# BMS_Adapter_Segment_millable.net
KiCad netlist of a schematic drawn in EAGLE
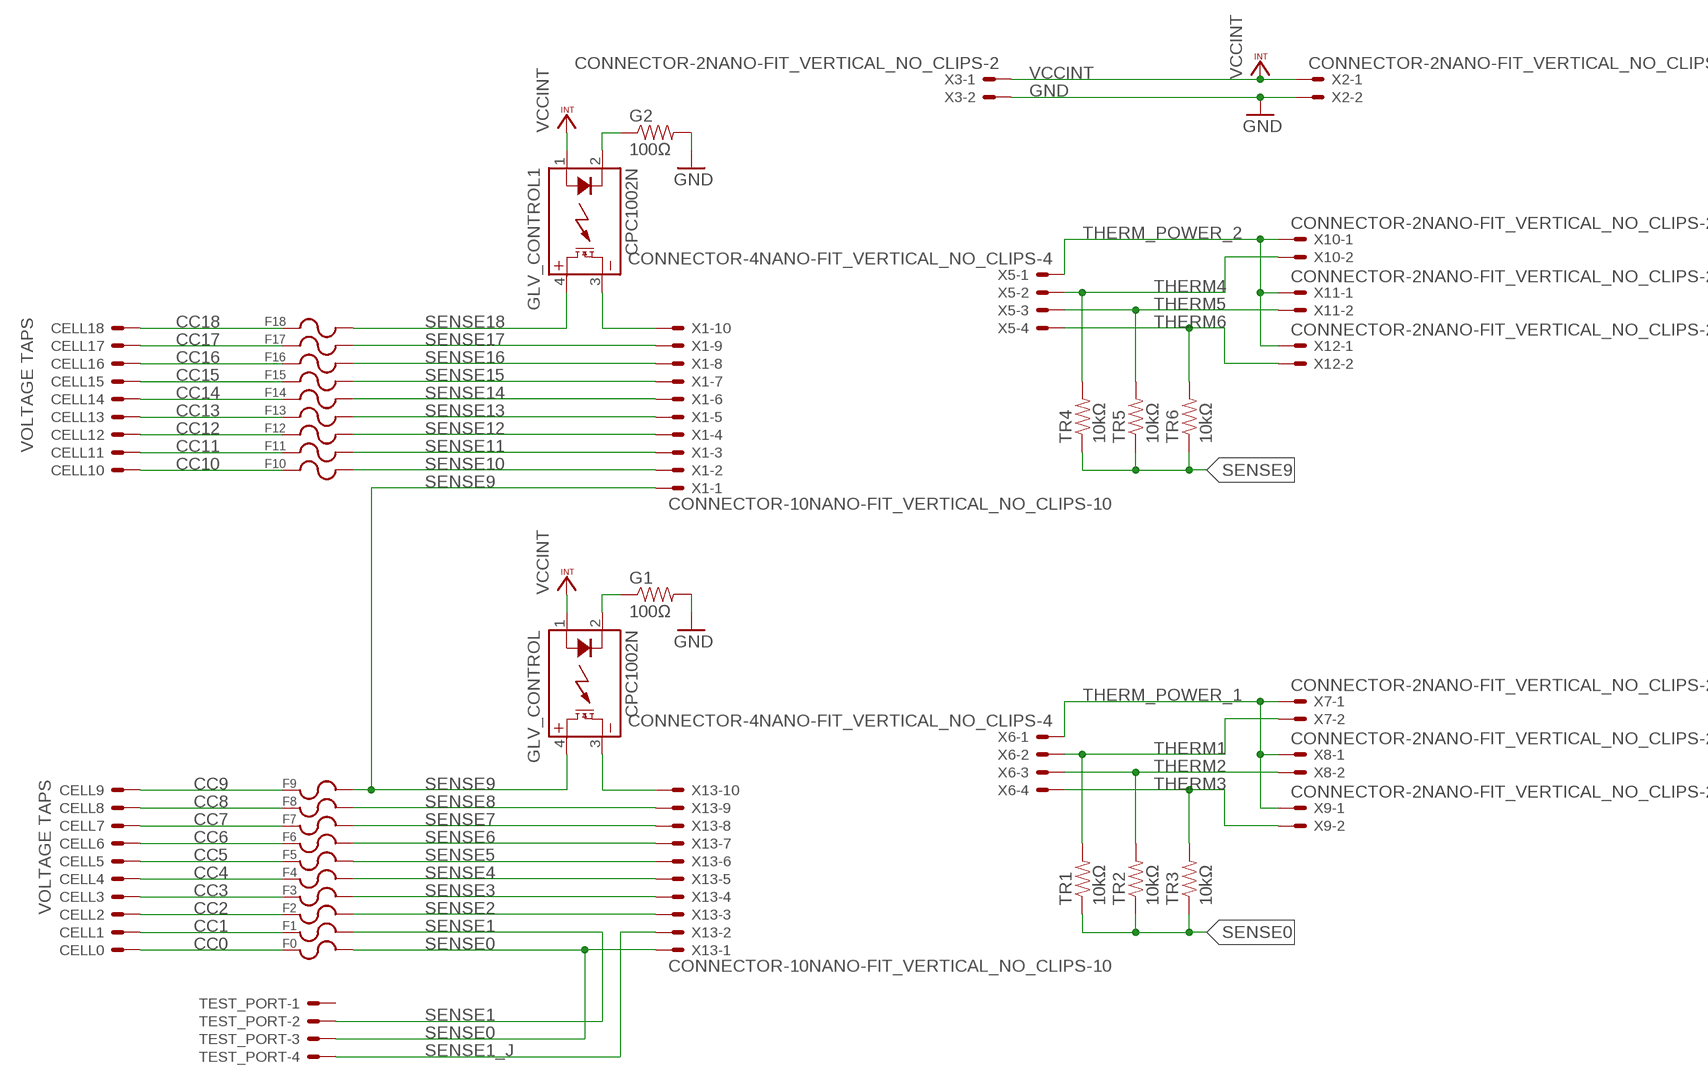
[diagram p0: schematic, sheet 1]

(export (version "E")
  (design (tool "Eeschema 10.0.6"))
  (components
    (comp (ref "CELL0")
      (value "BATTERY_SPRING_KEYSTONE5222")
      (footprint "eagle-import:KEYSTONE5222")
      (libsource (lib "eagle-import") (part "BATTERY_SPRING_KEYSTONE5222"))
    )
    (comp (ref "CELL1")
      (value "BATTERY_SPRING_KEYSTONE5222")
      (footprint "eagle-import:KEYSTONE5222")
      (libsource (lib "eagle-import") (part "BATTERY_SPRING_KEYSTONE5222"))
    )
    (comp (ref "CELL2")
      (value "BATTERY_SPRING_KEYSTONE5222")
      (footprint "eagle-import:KEYSTONE5222")
      (libsource (lib "eagle-import") (part "BATTERY_SPRING_KEYSTONE5222"))
    )
    (comp (ref "CELL3")
      (value "BATTERY_SPRING_KEYSTONE5222")
      (footprint "eagle-import:KEYSTONE5222")
      (libsource (lib "eagle-import") (part "BATTERY_SPRING_KEYSTONE5222"))
    )
    (comp (ref "CELL4")
      (value "BATTERY_SPRING_KEYSTONE5222")
      (footprint "eagle-import:KEYSTONE5222")
      (libsource (lib "eagle-import") (part "BATTERY_SPRING_KEYSTONE5222"))
    )
    (comp (ref "CELL5")
      (value "BATTERY_SPRING_KEYSTONE5222")
      (footprint "eagle-import:KEYSTONE5222")
      (libsource (lib "eagle-import") (part "BATTERY_SPRING_KEYSTONE5222"))
    )
    (comp (ref "CELL6")
      (value "BATTERY_SPRING_KEYSTONE5222")
      (footprint "eagle-import:KEYSTONE5222")
      (libsource (lib "eagle-import") (part "BATTERY_SPRING_KEYSTONE5222"))
    )
    (comp (ref "CELL7")
      (value "BATTERY_SPRING_KEYSTONE5222")
      (footprint "eagle-import:KEYSTONE5222")
      (libsource (lib "eagle-import") (part "BATTERY_SPRING_KEYSTONE5222"))
    )
    (comp (ref "CELL8")
      (value "BATTERY_SPRING_KEYSTONE5222")
      (footprint "eagle-import:KEYSTONE5222")
      (libsource (lib "eagle-import") (part "BATTERY_SPRING_KEYSTONE5222"))
    )
    (comp (ref "CELL9")
      (value "BATTERY_SPRING_KEYSTONE5222")
      (footprint "eagle-import:KEYSTONE5222")
      (libsource (lib "eagle-import") (part "BATTERY_SPRING_KEYSTONE5222"))
    )
    (comp (ref "CELL10")
      (value "BATTERY_SPRING_KEYSTONE5222")
      (footprint "eagle-import:KEYSTONE5222")
      (libsource (lib "eagle-import") (part "BATTERY_SPRING_KEYSTONE5222"))
    )
    (comp (ref "CELL11")
      (value "BATTERY_SPRING_KEYSTONE5222")
      (footprint "eagle-import:KEYSTONE5222")
      (libsource (lib "eagle-import") (part "BATTERY_SPRING_KEYSTONE5222"))
    )
    (comp (ref "CELL12")
      (value "BATTERY_SPRING_KEYSTONE5222")
      (footprint "eagle-import:KEYSTONE5222")
      (libsource (lib "eagle-import") (part "BATTERY_SPRING_KEYSTONE5222"))
    )
    (comp (ref "CELL13")
      (value "BATTERY_SPRING_KEYSTONE5222")
      (footprint "eagle-import:KEYSTONE5222")
      (libsource (lib "eagle-import") (part "BATTERY_SPRING_KEYSTONE5222"))
    )
    (comp (ref "CELL14")
      (value "BATTERY_SPRING_KEYSTONE5222")
      (footprint "eagle-import:KEYSTONE5222")
      (libsource (lib "eagle-import") (part "BATTERY_SPRING_KEYSTONE5222"))
    )
    (comp (ref "CELL15")
      (value "BATTERY_SPRING_KEYSTONE5222")
      (footprint "eagle-import:KEYSTONE5222")
      (libsource (lib "eagle-import") (part "BATTERY_SPRING_KEYSTONE5222"))
    )
    (comp (ref "CELL16")
      (value "BATTERY_SPRING_KEYSTONE5222")
      (footprint "eagle-import:KEYSTONE5222")
      (libsource (lib "eagle-import") (part "BATTERY_SPRING_KEYSTONE5222"))
    )
    (comp (ref "CELL17")
      (value "BATTERY_SPRING_KEYSTONE5222")
      (footprint "eagle-import:KEYSTONE5222")
      (libsource (lib "eagle-import") (part "BATTERY_SPRING_KEYSTONE5222"))
    )
    (comp (ref "CELL18")
      (value "BATTERY_SPRING_KEYSTONE5222")
      (footprint "eagle-import:KEYSTONE5222")
      (libsource (lib "eagle-import") (part "BATTERY_SPRING_KEYSTONE5222"))
    )
    (comp (ref "F0")
      (value "0751.0110_FUSE_CLIP")
      (footprint "eagle-import:0751.0110")
      (libsource (lib "eagle-import") (part "0751.0110_FUSE_CLIP"))
    )
    (comp (ref "F1")
      (value "0751.0110_FUSE_CLIP")
      (footprint "eagle-import:0751.0110")
      (libsource (lib "eagle-import") (part "0751.0110_FUSE_CLIP"))
    )
    (comp (ref "F2")
      (value "0751.0110_FUSE_CLIP")
      (footprint "eagle-import:0751.0110")
      (libsource (lib "eagle-import") (part "0751.0110_FUSE_CLIP"))
    )
    (comp (ref "F3")
      (value "0751.0110_FUSE_CLIP")
      (footprint "eagle-import:0751.0110")
      (libsource (lib "eagle-import") (part "0751.0110_FUSE_CLIP"))
    )
    (comp (ref "F4")
      (value "0751.0110_FUSE_CLIP")
      (footprint "eagle-import:0751.0110")
      (libsource (lib "eagle-import") (part "0751.0110_FUSE_CLIP"))
    )
    (comp (ref "F5")
      (value "0751.0110_FUSE_CLIP")
      (footprint "eagle-import:0751.0110")
      (libsource (lib "eagle-import") (part "0751.0110_FUSE_CLIP"))
    )
    (comp (ref "F6")
      (value "0751.0110_FUSE_CLIP")
      (footprint "eagle-import:0751.0110")
      (libsource (lib "eagle-import") (part "0751.0110_FUSE_CLIP"))
    )
    (comp (ref "F7")
      (value "0751.0110_FUSE_CLIP")
      (footprint "eagle-import:0751.0110")
      (libsource (lib "eagle-import") (part "0751.0110_FUSE_CLIP"))
    )
    (comp (ref "F8")
      (value "0751.0110_FUSE_CLIP")
      (footprint "eagle-import:0751.0110")
      (libsource (lib "eagle-import") (part "0751.0110_FUSE_CLIP"))
    )
    (comp (ref "F9")
      (value "0751.0110_FUSE_CLIP")
      (footprint "eagle-import:0751.0110")
      (libsource (lib "eagle-import") (part "0751.0110_FUSE_CLIP"))
    )
    (comp (ref "F10")
      (value "0751.0110_FUSE_CLIP")
      (footprint "eagle-import:0751.0110")
      (libsource (lib "eagle-import") (part "0751.0110_FUSE_CLIP"))
    )
    (comp (ref "F11")
      (value "0751.0110_FUSE_CLIP")
      (footprint "eagle-import:0751.0110")
      (libsource (lib "eagle-import") (part "0751.0110_FUSE_CLIP"))
    )
    (comp (ref "F12")
      (value "0751.0110_FUSE_CLIP")
      (footprint "eagle-import:0751.0110")
      (libsource (lib "eagle-import") (part "0751.0110_FUSE_CLIP"))
    )
    (comp (ref "F13")
      (value "0751.0110_FUSE_CLIP")
      (footprint "eagle-import:0751.0110")
      (libsource (lib "eagle-import") (part "0751.0110_FUSE_CLIP"))
    )
    (comp (ref "F14")
      (value "0751.0110_FUSE_CLIP")
      (footprint "eagle-import:0751.0110")
      (libsource (lib "eagle-import") (part "0751.0110_FUSE_CLIP"))
    )
    (comp (ref "F15")
      (value "0751.0110_FUSE_CLIP")
      (footprint "eagle-import:0751.0110")
      (libsource (lib "eagle-import") (part "0751.0110_FUSE_CLIP"))
    )
    (comp (ref "F16")
      (value "0751.0110_FUSE_CLIP")
      (footprint "eagle-import:0751.0110")
      (libsource (lib "eagle-import") (part "0751.0110_FUSE_CLIP"))
    )
    (comp (ref "F17")
      (value "0751.0110_FUSE_CLIP")
      (footprint "eagle-import:0751.0110")
      (libsource (lib "eagle-import") (part "0751.0110_FUSE_CLIP"))
    )
    (comp (ref "F18")
      (value "0751.0110_FUSE_CLIP")
      (footprint "eagle-import:0751.0110")
      (libsource (lib "eagle-import") (part "0751.0110_FUSE_CLIP"))
    )
    (comp (ref "G1")
      (value "100Ω")
      (footprint "eagle-import:0805")
      (libsource (lib "eagle-import") (part "RESISTOR0805-RES"))
    )
    (comp (ref "G2")
      (value "100Ω")
      (footprint "eagle-import:0805")
      (libsource (lib "eagle-import") (part "RESISTOR0805-RES"))
    )
    (comp (ref "GLV_CONTROL")
      (value "CPC1002N")
      (footprint "eagle-import:SOP04")
      (libsource (lib "eagle-import") (part "CPC1002N"))
    )
    (comp (ref "GLV_CONTROL1")
      (value "CPC1002N")
      (footprint "eagle-import:SOP04")
      (libsource (lib "eagle-import") (part "CPC1002N"))
    )
    (comp (ref "TEST_PORT")
      (value "MINIFIT_5566-4")
      (footprint "eagle-import:MINIFIT_5566-4")
      (libsource (lib "eagle-import") (part "MINIFIT_5566-4"))
    )
    (comp (ref "TR1")
      (value "10kΩ")
      (footprint "eagle-import:0805")
      (libsource (lib "eagle-import") (part "RESISTOR0805-RES"))
    )
    (comp (ref "TR2")
      (value "10kΩ")
      (footprint "eagle-import:0805")
      (libsource (lib "eagle-import") (part "RESISTOR0805-RES"))
    )
    (comp (ref "TR3")
      (value "10kΩ")
      (footprint "eagle-import:0805")
      (libsource (lib "eagle-import") (part "RESISTOR0805-RES"))
    )
    (comp (ref "TR4")
      (value "10kΩ")
      (footprint "eagle-import:0805")
      (libsource (lib "eagle-import") (part "RESISTOR0805-RES"))
    )
    (comp (ref "TR5")
      (value "10kΩ")
      (footprint "eagle-import:0805")
      (libsource (lib "eagle-import") (part "RESISTOR0805-RES"))
    )
    (comp (ref "TR6")
      (value "10kΩ")
      (footprint "eagle-import:0805")
      (libsource (lib "eagle-import") (part "RESISTOR0805-RES"))
    )
    (comp (ref "X1")
      (value "CONNECTOR-10NANO-FIT_VERTICAL_NO_CLIPS-10")
      (footprint "eagle-import:NANO-FIT_VERTICAL_NO_CLIPS-10")
      (libsource (lib "eagle-import") (part "CONNECTOR-10NANO-FIT_VERTICAL_NO_CLIPS-10"))
    )
    (comp (ref "X2")
      (value "CONNECTOR-2NANO-FIT_VERTICAL_NO_CLIPS-2")
      (footprint "eagle-import:NANO-FIT_VERTICAL_NO_CLIPS-2")
      (libsource (lib "eagle-import") (part "CONNECTOR-2NANO-FIT_VERTICAL_NO_CLIPS-2"))
    )
    (comp (ref "X3")
      (value "CONNECTOR-2NANO-FIT_VERTICAL_NO_CLIPS-2")
      (footprint "eagle-import:NANO-FIT_VERTICAL_NO_CLIPS-2")
      (libsource (lib "eagle-import") (part "CONNECTOR-2NANO-FIT_VERTICAL_NO_CLIPS-2"))
    )
    (comp (ref "X5")
      (value "CONNECTOR-4NANO-FIT_VERTICAL_NO_CLIPS-4")
      (footprint "eagle-import:NANO-FIT_VERTICAL_NO_CLIPS-4")
      (libsource (lib "eagle-import") (part "CONNECTOR-4NANO-FIT_VERTICAL_NO_CLIPS-4"))
    )
    (comp (ref "X6")
      (value "CONNECTOR-4NANO-FIT_VERTICAL_NO_CLIPS-4")
      (footprint "eagle-import:NANO-FIT_VERTICAL_NO_CLIPS-4")
      (libsource (lib "eagle-import") (part "CONNECTOR-4NANO-FIT_VERTICAL_NO_CLIPS-4"))
    )
    (comp (ref "X7")
      (value "CONNECTOR-2NANO-FIT_VERTICAL_NO_CLIPS-2")
      (footprint "eagle-import:NANO-FIT_VERTICAL_NO_CLIPS-2")
      (libsource (lib "eagle-import") (part "CONNECTOR-2NANO-FIT_VERTICAL_NO_CLIPS-2"))
    )
    (comp (ref "X8")
      (value "CONNECTOR-2NANO-FIT_VERTICAL_NO_CLIPS-2")
      (footprint "eagle-import:NANO-FIT_VERTICAL_NO_CLIPS-2")
      (libsource (lib "eagle-import") (part "CONNECTOR-2NANO-FIT_VERTICAL_NO_CLIPS-2"))
    )
    (comp (ref "X9")
      (value "CONNECTOR-2NANO-FIT_VERTICAL_NO_CLIPS-2")
      (footprint "eagle-import:NANO-FIT_VERTICAL_NO_CLIPS-2")
      (libsource (lib "eagle-import") (part "CONNECTOR-2NANO-FIT_VERTICAL_NO_CLIPS-2"))
    )
    (comp (ref "X10")
      (value "CONNECTOR-2NANO-FIT_VERTICAL_NO_CLIPS-2")
      (footprint "eagle-import:NANO-FIT_VERTICAL_NO_CLIPS-2")
      (libsource (lib "eagle-import") (part "CONNECTOR-2NANO-FIT_VERTICAL_NO_CLIPS-2"))
    )
    (comp (ref "X11")
      (value "CONNECTOR-2NANO-FIT_VERTICAL_NO_CLIPS-2")
      (footprint "eagle-import:NANO-FIT_VERTICAL_NO_CLIPS-2")
      (libsource (lib "eagle-import") (part "CONNECTOR-2NANO-FIT_VERTICAL_NO_CLIPS-2"))
    )
    (comp (ref "X12")
      (value "CONNECTOR-2NANO-FIT_VERTICAL_NO_CLIPS-2")
      (footprint "eagle-import:NANO-FIT_VERTICAL_NO_CLIPS-2")
      (libsource (lib "eagle-import") (part "CONNECTOR-2NANO-FIT_VERTICAL_NO_CLIPS-2"))
    )
    (comp (ref "X13")
      (value "CONNECTOR-10NANO-FIT_VERTICAL_NO_CLIPS-10")
      (footprint "eagle-import:NANO-FIT_VERTICAL_NO_CLIPS-10")
      (libsource (lib "eagle-import") (part "CONNECTOR-10NANO-FIT_VERTICAL_NO_CLIPS-10"))
    )
  )
  (nets
    (net (code "1") (name "/CC0") (class "Default")
      (node (ref "CELL0") (pin "P$1") (pinfunction "S_P$1") (pintype "passive"))
      (node (ref "F0") (pin "L1") (pinfunction "1_L1") (pintype "bidirectional"))
      (node (ref "F0") (pin "L2") (pinfunction "1_L2") (pintype "bidirectional"))
    )
    (net (code "2") (name "/CC1") (class "Default")
      (node (ref "CELL1") (pin "P$1") (pinfunction "S_P$1") (pintype "passive"))
      (node (ref "F1") (pin "L1") (pinfunction "1_L1") (pintype "bidirectional"))
      (node (ref "F1") (pin "L2") (pinfunction "1_L2") (pintype "bidirectional"))
    )
    (net (code "3") (name "/CC2") (class "Default")
      (node (ref "CELL2") (pin "P$1") (pinfunction "S_P$1") (pintype "passive"))
      (node (ref "F2") (pin "L1") (pinfunction "1_L1") (pintype "bidirectional"))
      (node (ref "F2") (pin "L2") (pinfunction "1_L2") (pintype "bidirectional"))
    )
    (net (code "4") (name "/CC3") (class "Default")
      (node (ref "CELL3") (pin "P$1") (pinfunction "S_P$1") (pintype "passive"))
      (node (ref "F3") (pin "L1") (pinfunction "1_L1") (pintype "bidirectional"))
      (node (ref "F3") (pin "L2") (pinfunction "1_L2") (pintype "bidirectional"))
    )
    (net (code "5") (name "/CC4") (class "Default")
      (node (ref "CELL4") (pin "P$1") (pinfunction "S_P$1") (pintype "passive"))
      (node (ref "F4") (pin "L1") (pinfunction "1_L1") (pintype "bidirectional"))
      (node (ref "F4") (pin "L2") (pinfunction "1_L2") (pintype "bidirectional"))
    )
    (net (code "6") (name "/CC5") (class "Default")
      (node (ref "CELL5") (pin "P$1") (pinfunction "S_P$1") (pintype "passive"))
      (node (ref "F5") (pin "L1") (pinfunction "1_L1") (pintype "bidirectional"))
      (node (ref "F5") (pin "L2") (pinfunction "1_L2") (pintype "bidirectional"))
    )
    (net (code "7") (name "/CC6") (class "Default")
      (node (ref "CELL6") (pin "P$1") (pinfunction "S_P$1") (pintype "passive"))
      (node (ref "F6") (pin "L1") (pinfunction "1_L1") (pintype "bidirectional"))
      (node (ref "F6") (pin "L2") (pinfunction "1_L2") (pintype "bidirectional"))
    )
    (net (code "8") (name "/CC7") (class "Default")
      (node (ref "CELL7") (pin "P$1") (pinfunction "S_P$1") (pintype "passive"))
      (node (ref "F7") (pin "L1") (pinfunction "1_L1") (pintype "bidirectional"))
      (node (ref "F7") (pin "L2") (pinfunction "1_L2") (pintype "bidirectional"))
    )
    (net (code "9") (name "/CC8") (class "Default")
      (node (ref "CELL8") (pin "P$1") (pinfunction "S_P$1") (pintype "passive"))
      (node (ref "F8") (pin "L1") (pinfunction "1_L1") (pintype "bidirectional"))
      (node (ref "F8") (pin "L2") (pinfunction "1_L2") (pintype "bidirectional"))
    )
    (net (code "10") (name "/CC9") (class "Default")
      (node (ref "CELL9") (pin "P$1") (pinfunction "S_P$1") (pintype "passive"))
      (node (ref "F9") (pin "L1") (pinfunction "1_L1") (pintype "bidirectional"))
      (node (ref "F9") (pin "L2") (pinfunction "1_L2") (pintype "bidirectional"))
    )
    (net (code "11") (name "/CC10") (class "Default")
      (node (ref "CELL10") (pin "P$1") (pinfunction "S_P$1") (pintype "passive"))
      (node (ref "F10") (pin "L1") (pinfunction "1_L1") (pintype "bidirectional"))
      (node (ref "F10") (pin "L2") (pinfunction "1_L2") (pintype "bidirectional"))
    )
    (net (code "12") (name "/CC11") (class "Default")
      (node (ref "CELL11") (pin "P$1") (pinfunction "S_P$1") (pintype "passive"))
      (node (ref "F11") (pin "L1") (pinfunction "1_L1") (pintype "bidirectional"))
      (node (ref "F11") (pin "L2") (pinfunction "1_L2") (pintype "bidirectional"))
    )
    (net (code "13") (name "/CC12") (class "Default")
      (node (ref "CELL12") (pin "P$1") (pinfunction "S_P$1") (pintype "passive"))
      (node (ref "F12") (pin "L1") (pinfunction "1_L1") (pintype "bidirectional"))
      (node (ref "F12") (pin "L2") (pinfunction "1_L2") (pintype "bidirectional"))
    )
    (net (code "14") (name "/CC13") (class "Default")
      (node (ref "CELL13") (pin "P$1") (pinfunction "S_P$1") (pintype "passive"))
      (node (ref "F13") (pin "L1") (pinfunction "1_L1") (pintype "bidirectional"))
      (node (ref "F13") (pin "L2") (pinfunction "1_L2") (pintype "bidirectional"))
    )
    (net (code "15") (name "/CC14") (class "Default")
      (node (ref "CELL14") (pin "P$1") (pinfunction "S_P$1") (pintype "passive"))
      (node (ref "F14") (pin "L1") (pinfunction "1_L1") (pintype "bidirectional"))
      (node (ref "F14") (pin "L2") (pinfunction "1_L2") (pintype "bidirectional"))
    )
    (net (code "16") (name "/CC15") (class "Default")
      (node (ref "CELL15") (pin "P$1") (pinfunction "S_P$1") (pintype "passive"))
      (node (ref "F15") (pin "L1") (pinfunction "1_L1") (pintype "bidirectional"))
      (node (ref "F15") (pin "L2") (pinfunction "1_L2") (pintype "bidirectional"))
    )
    (net (code "17") (name "/CC16") (class "Default")
      (node (ref "CELL16") (pin "P$1") (pinfunction "S_P$1") (pintype "passive"))
      (node (ref "F16") (pin "L1") (pinfunction "1_L1") (pintype "bidirectional"))
      (node (ref "F16") (pin "L2") (pinfunction "1_L2") (pintype "bidirectional"))
    )
    (net (code "18") (name "/CC17") (class "Default")
      (node (ref "CELL17") (pin "P$1") (pinfunction "S_P$1") (pintype "passive"))
      (node (ref "F17") (pin "L1") (pinfunction "1_L1") (pintype "bidirectional"))
      (node (ref "F17") (pin "L2") (pinfunction "1_L2") (pintype "bidirectional"))
    )
    (net (code "19") (name "/CC18") (class "Default")
      (node (ref "CELL18") (pin "P$1") (pinfunction "S_P$1") (pintype "passive"))
      (node (ref "F18") (pin "L1") (pinfunction "1_L1") (pintype "bidirectional"))
      (node (ref "F18") (pin "L2") (pinfunction "1_L2") (pintype "bidirectional"))
    )
    (net (code "20") (name "/SENSE1") (class "Default")
      (node (ref "F1") (pin "R1") (pinfunction "2_R1") (pintype "bidirectional"))
      (node (ref "F1") (pin "R2") (pinfunction "2_R2") (pintype "bidirectional"))
      (node (ref "TEST_PORT") (pin "2") (pinfunction "S_2") (pintype "passive"))
    )
    (net (code "21") (name "/SENSE1_J") (class "Default")
      (node (ref "TEST_PORT") (pin "4") (pinfunction "S_4") (pintype "passive"))
      (node (ref "X13") (pin "P$2") (pinfunction "S_P$2") (pintype "passive"))
    )
    (net (code "22") (name "/SENSE2") (class "Default")
      (node (ref "F2") (pin "R1") (pinfunction "2_R1") (pintype "bidirectional"))
      (node (ref "F2") (pin "R2") (pinfunction "2_R2") (pintype "bidirectional"))
      (node (ref "X13") (pin "P$3") (pinfunction "S_P$3") (pintype "passive"))
    )
    (net (code "23") (name "/SENSE3") (class "Default")
      (node (ref "F3") (pin "R1") (pinfunction "2_R1") (pintype "bidirectional"))
      (node (ref "F3") (pin "R2") (pinfunction "2_R2") (pintype "bidirectional"))
      (node (ref "X13") (pin "P$4") (pinfunction "S_P$4") (pintype "passive"))
    )
    (net (code "24") (name "/SENSE4") (class "Default")
      (node (ref "F4") (pin "R1") (pinfunction "2_R1") (pintype "bidirectional"))
      (node (ref "F4") (pin "R2") (pinfunction "2_R2") (pintype "bidirectional"))
      (node (ref "X13") (pin "P$5") (pinfunction "S_P$5") (pintype "passive"))
    )
    (net (code "25") (name "/SENSE5") (class "Default")
      (node (ref "F5") (pin "R1") (pinfunction "2_R1") (pintype "bidirectional"))
      (node (ref "F5") (pin "R2") (pinfunction "2_R2") (pintype "bidirectional"))
      (node (ref "X13") (pin "P$6") (pinfunction "S_P$6") (pintype "passive"))
    )
    (net (code "26") (name "/SENSE6") (class "Default")
      (node (ref "F6") (pin "R1") (pinfunction "2_R1") (pintype "bidirectional"))
      (node (ref "F6") (pin "R2") (pinfunction "2_R2") (pintype "bidirectional"))
      (node (ref "X13") (pin "P$7") (pinfunction "S_P$7") (pintype "passive"))
    )
    (net (code "27") (name "/SENSE7") (class "Default")
      (node (ref "F7") (pin "R1") (pinfunction "2_R1") (pintype "bidirectional"))
      (node (ref "F7") (pin "R2") (pinfunction "2_R2") (pintype "bidirectional"))
      (node (ref "X13") (pin "P$8") (pinfunction "S_P$8") (pintype "passive"))
    )
    (net (code "28") (name "/SENSE8") (class "Default")
      (node (ref "F8") (pin "R1") (pinfunction "2_R1") (pintype "bidirectional"))
      (node (ref "F8") (pin "R2") (pinfunction "2_R2") (pintype "bidirectional"))
      (node (ref "X13") (pin "P$9") (pinfunction "S_P$9") (pintype "passive"))
    )
    (net (code "29") (name "/SENSE10") (class "Default")
      (node (ref "F10") (pin "R1") (pinfunction "2_R1") (pintype "bidirectional"))
      (node (ref "F10") (pin "R2") (pinfunction "2_R2") (pintype "bidirectional"))
      (node (ref "X1") (pin "P$2") (pinfunction "S_P$2") (pintype "passive"))
    )
    (net (code "30") (name "/SENSE11") (class "Default")
      (node (ref "F11") (pin "R1") (pinfunction "2_R1") (pintype "bidirectional"))
      (node (ref "F11") (pin "R2") (pinfunction "2_R2") (pintype "bidirectional"))
      (node (ref "X1") (pin "P$3") (pinfunction "S_P$3") (pintype "passive"))
    )
    (net (code "31") (name "/SENSE12") (class "Default")
      (node (ref "F12") (pin "R1") (pinfunction "2_R1") (pintype "bidirectional"))
      (node (ref "F12") (pin "R2") (pinfunction "2_R2") (pintype "bidirectional"))
      (node (ref "X1") (pin "P$4") (pinfunction "S_P$4") (pintype "passive"))
    )
    (net (code "32") (name "/SENSE13") (class "Default")
      (node (ref "F13") (pin "R1") (pinfunction "2_R1") (pintype "bidirectional"))
      (node (ref "F13") (pin "R2") (pinfunction "2_R2") (pintype "bidirectional"))
      (node (ref "X1") (pin "P$5") (pinfunction "S_P$5") (pintype "passive"))
    )
    (net (code "33") (name "/SENSE14") (class "Default")
      (node (ref "F14") (pin "R1") (pinfunction "2_R1") (pintype "bidirectional"))
      (node (ref "F14") (pin "R2") (pinfunction "2_R2") (pintype "bidirectional"))
      (node (ref "X1") (pin "P$6") (pinfunction "S_P$6") (pintype "passive"))
    )
    (net (code "34") (name "/SENSE15") (class "Default")
      (node (ref "F15") (pin "R1") (pinfunction "2_R1") (pintype "bidirectional"))
      (node (ref "F15") (pin "R2") (pinfunction "2_R2") (pintype "bidirectional"))
      (node (ref "X1") (pin "P$7") (pinfunction "S_P$7") (pintype "passive"))
    )
    (net (code "35") (name "/SENSE16") (class "Default")
      (node (ref "F16") (pin "R1") (pinfunction "2_R1") (pintype "bidirectional"))
      (node (ref "F16") (pin "R2") (pinfunction "2_R2") (pintype "bidirectional"))
      (node (ref "X1") (pin "P$8") (pinfunction "S_P$8") (pintype "passive"))
    )
    (net (code "36") (name "/SENSE17") (class "Default")
      (node (ref "F17") (pin "R1") (pinfunction "2_R1") (pintype "bidirectional"))
      (node (ref "F17") (pin "R2") (pinfunction "2_R2") (pintype "bidirectional"))
      (node (ref "X1") (pin "P$9") (pinfunction "S_P$9") (pintype "passive"))
    )
    (net (code "37") (name "/SENSE18") (class "Default")
      (node (ref "F18") (pin "R1") (pinfunction "2_R1") (pintype "bidirectional"))
      (node (ref "F18") (pin "R2") (pinfunction "2_R2") (pintype "bidirectional"))
      (node (ref "GLV_CONTROL1") (pin "4") (pinfunction "DC+_4") (pintype "passive"))
    )
    (net (code "38") (name "/THERM1") (class "Default")
      (node (ref "TR1") (pin "2") (pinfunction "2_2") (pintype "passive"))
      (node (ref "X6") (pin "P$2") (pinfunction "S_P$2") (pintype "passive"))
      (node (ref "X7") (pin "P$2") (pinfunction "S_P$2") (pintype "passive"))
    )
    (net (code "39") (name "/THERM2") (class "Default")
      (node (ref "TR2") (pin "2") (pinfunction "2_2") (pintype "passive"))
      (node (ref "X6") (pin "P$3") (pinfunction "S_P$3") (pintype "passive"))
      (node (ref "X8") (pin "P$2") (pinfunction "S_P$2") (pintype "passive"))
    )
    (net (code "40") (name "/THERM3") (class "Default")
      (node (ref "TR3") (pin "2") (pinfunction "2_2") (pintype "passive"))
      (node (ref "X6") (pin "P$4") (pinfunction "S_P$4") (pintype "passive"))
      (node (ref "X9") (pin "P$2") (pinfunction "S_P$2") (pintype "passive"))
    )
    (net (code "41") (name "/THERM4") (class "Default")
      (node (ref "TR4") (pin "2") (pinfunction "2_2") (pintype "passive"))
      (node (ref "X10") (pin "P$2") (pinfunction "S_P$2") (pintype "passive"))
      (node (ref "X5") (pin "P$2") (pinfunction "S_P$2") (pintype "passive"))
    )
    (net (code "42") (name "/THERM5") (class "Default")
      (node (ref "TR5") (pin "2") (pinfunction "2_2") (pintype "passive"))
      (node (ref "X11") (pin "P$2") (pinfunction "S_P$2") (pintype "passive"))
      (node (ref "X5") (pin "P$3") (pinfunction "S_P$3") (pintype "passive"))
    )
    (net (code "43") (name "/THERM6") (class "Default")
      (node (ref "TR6") (pin "2") (pinfunction "2_2") (pintype "passive"))
      (node (ref "X12") (pin "P$2") (pinfunction "S_P$2") (pintype "passive"))
      (node (ref "X5") (pin "P$4") (pinfunction "S_P$4") (pintype "passive"))
    )
    (net (code "44") (name "/THERM_POWER_1") (class "Default")
      (node (ref "X6") (pin "P$1") (pinfunction "S_P$1") (pintype "passive"))
      (node (ref "X7") (pin "P$1") (pinfunction "S_P$1") (pintype "passive"))
      (node (ref "X8") (pin "P$1") (pinfunction "S_P$1") (pintype "passive"))
      (node (ref "X9") (pin "P$1") (pinfunction "S_P$1") (pintype "passive"))
    )
    (net (code "45") (name "/THERM_POWER_2") (class "Default")
      (node (ref "X10") (pin "P$1") (pinfunction "S_P$1") (pintype "passive"))
      (node (ref "X11") (pin "P$1") (pinfunction "S_P$1") (pintype "passive"))
      (node (ref "X12") (pin "P$1") (pinfunction "S_P$1") (pintype "passive"))
      (node (ref "X5") (pin "P$1") (pinfunction "S_P$1") (pintype "passive"))
    )
    (net (code "46") (name "GND") (class "Default")
      (node (ref "G1") (pin "2") (pinfunction "2_2") (pintype "passive"))
      (node (ref "G2") (pin "2") (pinfunction "2_2") (pintype "passive"))
      (node (ref "X2") (pin "P$2") (pinfunction "S_P$2") (pintype "passive"))
      (node (ref "X3") (pin "P$2") (pinfunction "S_P$2") (pintype "passive"))
    )
    (net (code "47") (name "Net-(GLV_CONTROL-CONTROL-)") (class "Default")
      (node (ref "G1") (pin "1") (pinfunction "1_1") (pintype "passive"))
      (node (ref "GLV_CONTROL") (pin "2") (pinfunction "CONTROL-_2") (pintype "passive"))
    )
    (net (code "48") (name "Net-(GLV_CONTROL-DC-)") (class "Default")
      (node (ref "GLV_CONTROL") (pin "3") (pinfunction "DC-_3") (pintype "passive"))
      (node (ref "X13") (pin "P$10") (pinfunction "S_P$10") (pintype "passive"))
    )
    (net (code "49") (name "Net-(GLV_CONTROL1-CONTROL-)") (class "Default")
      (node (ref "G2") (pin "1") (pinfunction "1_1") (pintype "passive"))
      (node (ref "GLV_CONTROL1") (pin "2") (pinfunction "CONTROL-_2") (pintype "passive"))
    )
    (net (code "50") (name "Net-(GLV_CONTROL1-DC-)") (class "Default")
      (node (ref "GLV_CONTROL1") (pin "3") (pinfunction "DC-_3") (pintype "passive"))
      (node (ref "X1") (pin "P$10") (pinfunction "S_P$10") (pintype "passive"))
    )
    (net (code "51") (name "SENSE0") (class "Default")
      (node (ref "F0") (pin "R1") (pinfunction "2_R1") (pintype "bidirectional"))
      (node (ref "F0") (pin "R2") (pinfunction "2_R2") (pintype "bidirectional"))
      (node (ref "TEST_PORT") (pin "3") (pinfunction "S_3") (pintype "passive"))
      (node (ref "TR1") (pin "1") (pinfunction "1_1") (pintype "passive"))
      (node (ref "TR2") (pin "1") (pinfunction "1_1") (pintype "passive"))
      (node (ref "TR3") (pin "1") (pinfunction "1_1") (pintype "passive"))
      (node (ref "X13") (pin "P$1") (pinfunction "S_P$1") (pintype "passive"))
    )
    (net (code "52") (name "SENSE9") (class "Default")
      (node (ref "F9") (pin "R1") (pinfunction "2_R1") (pintype "bidirectional"))
      (node (ref "F9") (pin "R2") (pinfunction "2_R2") (pintype "bidirectional"))
      (node (ref "GLV_CONTROL") (pin "4") (pinfunction "DC+_4") (pintype "passive"))
      (node (ref "TR4") (pin "1") (pinfunction "1_1") (pintype "passive"))
      (node (ref "TR5") (pin "1") (pinfunction "1_1") (pintype "passive"))
      (node (ref "TR6") (pin "1") (pinfunction "1_1") (pintype "passive"))
      (node (ref "X1") (pin "P$1") (pinfunction "S_P$1") (pintype "passive"))
    )
    (net (code "53") (name "VCCINT") (class "Default")
      (node (ref "GLV_CONTROL") (pin "1") (pinfunction "CONTROL+_1") (pintype "passive"))
      (node (ref "GLV_CONTROL1") (pin "1") (pinfunction "CONTROL+_1") (pintype "passive"))
      (node (ref "X2") (pin "P$1") (pinfunction "S_P$1") (pintype "passive"))
      (node (ref "X3") (pin "P$1") (pinfunction "S_P$1") (pintype "passive"))
    )
    (net (code "54") (name "unconnected-(TEST_PORTA-S-Pad1)") (class "Default")
      (node (ref "TEST_PORT") (pin "1") (pinfunction "S_1") (pintype "passive"))
    )
  )
)
